# LOCO-Control.net
KiCad netlist of a schematic drawn in EAGLE
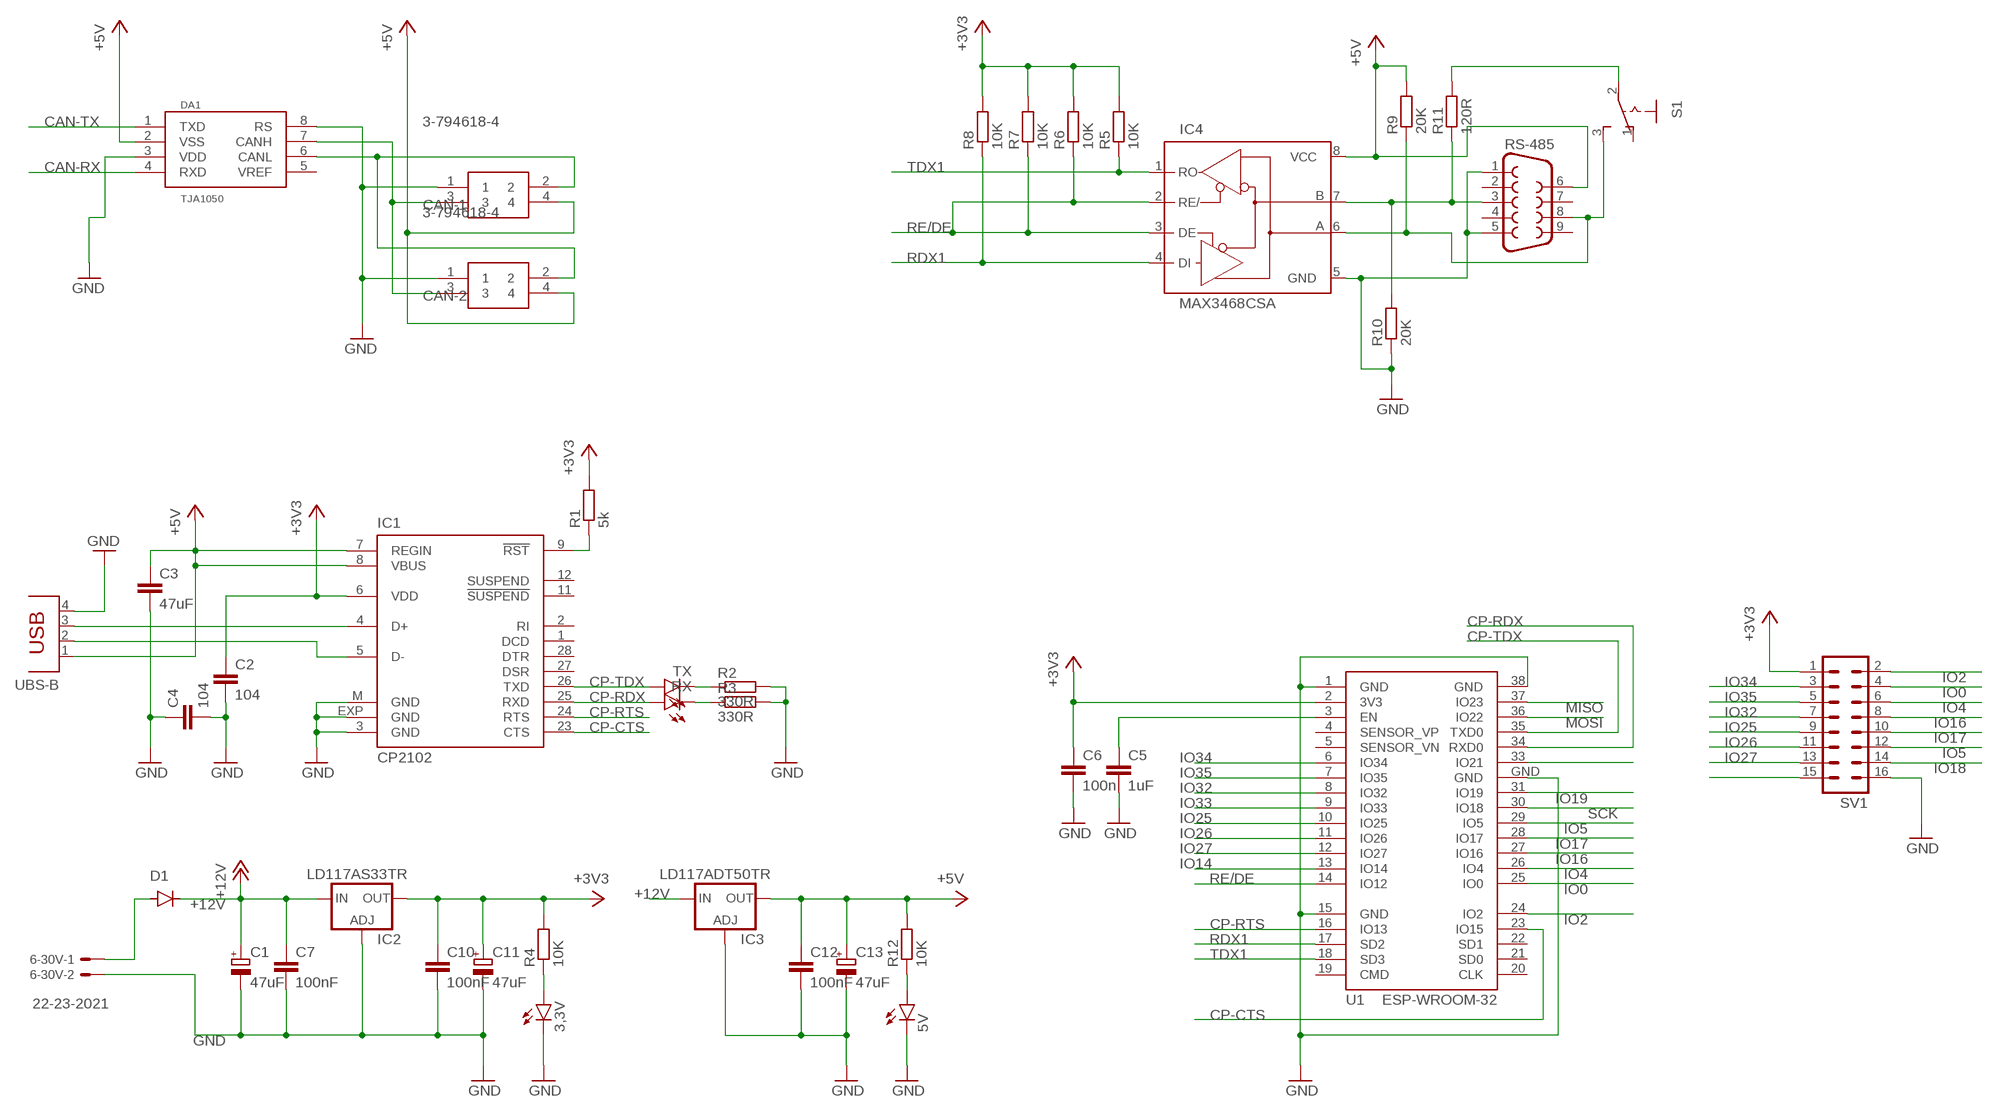
[diagram p0: schematic, sheet 1]

(export (version "E")
  (design (tool "Eeschema 10.0.6"))
  (components
    (comp (ref "3,3V")
      (value "LED")
      (footprint "eagle-import:SMARTLED-TTW")
      (libsource (lib "eagle-import") (part "LED"))
    )
    (comp (ref "5V")
      (value "LED")
      (footprint "eagle-import:SMARTLED-TTW")
      (libsource (lib "eagle-import") (part "LED"))
    )
    (comp (ref "6-30V")
      (value "22-23-2021")
      (footprint "eagle-import:22-23-2021")
      (fields (field (name "MF") "MOLEX"))
      (libsource (lib "eagle-import") (part "22-23-2021"))
    )
    (comp (ref "C1")
      (value "47uF")
      (footprint "eagle-import:B_3528-21R")
      (libsource (lib "eagle-import") (part "CPOL-EUB/3528-21R"))
    )
    (comp (ref "C2")
      (value "104")
      (footprint "eagle-import:C0402")
      (libsource (lib "eagle-import") (part "C-EUC0402"))
    )
    (comp (ref "C3")
      (value "47uF")
      (footprint "eagle-import:C0402")
      (libsource (lib "eagle-import") (part "C-EUC0402"))
    )
    (comp (ref "C4")
      (value "104")
      (footprint "eagle-import:C0402")
      (libsource (lib "eagle-import") (part "C-EUC0402"))
    )
    (comp (ref "C5")
      (value "1uF")
      (footprint "eagle-import:C0402")
      (libsource (lib "eagle-import") (part "C-EUC0402"))
    )
    (comp (ref "C6")
      (value "100n")
      (footprint "eagle-import:C0402")
      (libsource (lib "eagle-import") (part "C-EUC0402"))
    )
    (comp (ref "C7")
      (value "100nF")
      (footprint "eagle-import:C0402")
      (libsource (lib "eagle-import") (part "C-EUC0402"))
    )
    (comp (ref "C10")
      (value "100nF")
      (footprint "eagle-import:C0402")
      (libsource (lib "eagle-import") (part "C-EUC0402"))
    )
    (comp (ref "C11")
      (value "47uF")
      (footprint "eagle-import:B_3528-21R")
      (libsource (lib "eagle-import") (part "CPOL-EUB/3528-21R"))
    )
    (comp (ref "C12")
      (value "100nF")
      (footprint "eagle-import:C0402")
      (libsource (lib "eagle-import") (part "C-EUC0402"))
    )
    (comp (ref "C13")
      (value "47uF")
      (footprint "eagle-import:B_3528-21R")
      (libsource (lib "eagle-import") (part "CPOL-EUB/3528-21R"))
    )
    (comp (ref "CAN-1")
      (value "3-794618-4")
      (footprint "eagle-import:SHDRRA4W102P300_2X2_686X892X73")
      (libsource (lib "eagle-import") (part "3-794618-4"))
    )
    (comp (ref "CAN-2")
      (value "3-794618-4")
      (footprint "eagle-import:SHDRRA4W102P300_2X2_686X892X73")
      (libsource (lib "eagle-import") (part "3-794618-4"))
    )
    (comp (ref "D1")
      (value "DIODE-DO-214AC")
      (footprint "eagle-import:DO-214AC")
      (libsource (lib "eagle-import") (part "DIODE-DO-214AC"))
    )
    (comp (ref "DA1")
      (value "TJA1050")
      (footprint "eagle-import:SO08")
      (libsource (lib "eagle-import") (part "TJA1050"))
    )
    (comp (ref "IC1")
      (value "CP2102")
      (footprint "eagle-import:MLP28")
      (fields (field (name "MF") "FARNELL") (field (name "MPN") "CP2102-GM"))
      (libsource (lib "eagle-import") (part "CP2102"))
    )
    (comp (ref "IC2")
      (value "LD117AS33TR")
      (footprint "eagle-import:SOT223")
      (libsource (lib "eagle-import") (part "LD117A?S33TR"))
    )
    (comp (ref "IC3")
      (value "LD117ADT50TR")
      (footprint "eagle-import:DPACK")
      (libsource (lib "eagle-import") (part "LD117A?DT50TR"))
    )
    (comp (ref "IC4")
      (value "MAX3468CSA")
      (footprint "eagle-import:SO08")
      (fields (field (name "MPN") "MAX3468CSA+"))
      (libsource (lib "eagle-import") (part "MAX34SA68C"))
    )
    (comp (ref "R1")
      (value "5k")
      (footprint "eagle-import:MINI_MELF-0102R")
      (libsource (lib "eagle-import") (part "R-EU_MELF0102R"))
    )
    (comp (ref "R2")
      (value "330R")
      (footprint "eagle-import:MINI_MELF-0102R")
      (libsource (lib "eagle-import") (part "R-EU_MELF0102R"))
    )
    (comp (ref "R3")
      (value "330R")
      (footprint "eagle-import:MINI_MELF-0102R")
      (libsource (lib "eagle-import") (part "R-EU_MELF0102R"))
    )
    (comp (ref "R4")
      (value "10K")
      (footprint "eagle-import:MINI_MELF-0102R")
      (libsource (lib "eagle-import") (part "R-EU_MELF0102R"))
    )
    (comp (ref "R5")
      (value "10K")
      (footprint "eagle-import:MINI_MELF-0102R")
      (libsource (lib "eagle-import") (part "R-EU_MELF0102R"))
    )
    (comp (ref "R6")
      (value "10K")
      (footprint "eagle-import:MINI_MELF-0102R")
      (libsource (lib "eagle-import") (part "R-EU_MELF0102R"))
    )
    (comp (ref "R7")
      (value "10K")
      (footprint "eagle-import:MINI_MELF-0102R")
      (libsource (lib "eagle-import") (part "R-EU_MELF0102R"))
    )
    (comp (ref "R8")
      (value "10K")
      (footprint "eagle-import:MINI_MELF-0102R")
      (libsource (lib "eagle-import") (part "R-EU_MELF0102R"))
    )
    (comp (ref "R9")
      (value "20K")
      (footprint "eagle-import:MINI_MELF-0102R")
      (libsource (lib "eagle-import") (part "R-EU_MELF0102R"))
    )
    (comp (ref "R10")
      (value "20K")
      (footprint "eagle-import:MINI_MELF-0102R")
      (libsource (lib "eagle-import") (part "R-EU_MELF0102R"))
    )
    (comp (ref "R11")
      (value "120R")
      (footprint "eagle-import:MINI_MELF-0102R")
      (libsource (lib "eagle-import") (part "R-EU_MELF0102R"))
    )
    (comp (ref "R12")
      (value "10K")
      (footprint "eagle-import:MINI_MELF-0102R")
      (libsource (lib "eagle-import") (part "R-EU_MELF0102R"))
    )
    (comp (ref "RS-485")
      (value "F09H")
      (footprint "eagle-import:F09H")
      (libsource (lib "eagle-import") (part "F09H"))
    )
    (comp (ref "RX")
      (value "LED")
      (footprint "eagle-import:SMARTLED-TTW")
      (libsource (lib "eagle-import") (part "LED"))
    )
    (comp (ref "S1")
      (value "255SB")
      (footprint "eagle-import:255SB")
      (libsource (lib "eagle-import") (part "255SB"))
    )
    (comp (ref "SV1")
      (value "MA08-2")
      (footprint "eagle-import:MA08-2")
      (libsource (lib "eagle-import") (part "MA08-2"))
    )
    (comp (ref "TX")
      (value "LED")
      (footprint "eagle-import:SMARTLED-TTW")
      (libsource (lib "eagle-import") (part "LED"))
    )
    (comp (ref "U1")
      (value "ESP-WROOM-32")
      (footprint "eagle-import:ESP-WROOM-32")
      (libsource (lib "eagle-import") (part "ESP-WROOM-32"))
    )
    (comp (ref "UBS-B")
      (value "PN61729")
      (footprint "eagle-import:PN61729")
      (libsource (lib "eagle-import") (part "PN61729"))
    )
  )
  (nets
    (net (code "1") (name "+3V3") (class "Default")
      (node (ref "C10") (pin "1") (pinfunction "1_1") (pintype "passive"))
      (node (ref "C11") (pin "+") (pinfunction "+_+") (pintype "passive"))
      (node (ref "C2") (pin "1") (pinfunction "1_1") (pintype "passive"))
      (node (ref "C6") (pin "1") (pinfunction "1_1") (pintype "passive"))
      (node (ref "IC1") (pin "6") (pinfunction "VDD_6") (pintype "power_in"))
      (node (ref "IC2") (pin "4") (pinfunction "OUT_4") (pintype "passive"))
      (node (ref "R1") (pin "2") (pinfunction "2_2") (pintype "passive"))
      (node (ref "R4") (pin "2") (pinfunction "2_2") (pintype "passive"))
      (node (ref "R5") (pin "2") (pinfunction "2_2") (pintype "passive"))
      (node (ref "R6") (pin "2") (pinfunction "2_2") (pintype "passive"))
      (node (ref "R7") (pin "2") (pinfunction "2_2") (pintype "passive"))
      (node (ref "R8") (pin "2") (pinfunction "2_2") (pintype "passive"))
      (node (ref "SV1") (pin "1") (pinfunction "1_1") (pintype "passive"))
      (node (ref "U1") (pin "2") (pinfunction "3V3_2") (pintype "power_in"))
    )
    (net (code "2") (name "+5V") (class "Default")
      (node (ref "C12") (pin "1") (pinfunction "1_1") (pintype "passive"))
      (node (ref "C13") (pin "+") (pinfunction "+_+") (pintype "passive"))
      (node (ref "C3") (pin "1") (pinfunction "1_1") (pintype "passive"))
      (node (ref "CAN-1") (pin "4") (pinfunction "4_4") (pintype "bidirectional"))
      (node (ref "CAN-2") (pin "4") (pinfunction "4_4") (pintype "bidirectional"))
      (node (ref "DA1") (pin "2") (pinfunction "VSS_2") (pintype "power_in"))
      (node (ref "IC1") (pin "7") (pinfunction "REGIN_7") (pintype "passive"))
      (node (ref "IC1") (pin "8") (pinfunction "VBUS_8") (pintype "input"))
      (node (ref "IC3") (pin "4") (pinfunction "OUT_4") (pintype "passive"))
      (node (ref "IC4") (pin "8") (pinfunction "VCC_8") (pintype "power_in"))
      (node (ref "R12") (pin "2") (pinfunction "2_2") (pintype "passive"))
      (node (ref "R9") (pin "2") (pinfunction "2_2") (pintype "passive"))
      (node (ref "RS-485") (pin "6") (pinfunction "6_6") (pintype "passive"))
      (node (ref "UBS-B") (pin "1") (pinfunction "1_1") (pintype "passive"))
    )
    (net (code "3") (name "+12V") (class "Default")
      (node (ref "C1") (pin "+") (pinfunction "+_+") (pintype "passive"))
      (node (ref "C7") (pin "1") (pinfunction "1_1") (pintype "passive"))
      (node (ref "D1") (pin "C") (pinfunction "C_C") (pintype "passive"))
      (node (ref "IC2") (pin "3") (pinfunction "IN_3") (pintype "input"))
      (node (ref "IC3") (pin "3") (pinfunction "IN_3") (pintype "input"))
    )
    (net (code "4") (name "/CAN-RX") (class "Default")
      (node (ref "DA1") (pin "4") (pinfunction "RXD_4") (pintype "output"))
    )
    (net (code "5") (name "/CAN-TX") (class "Default")
      (node (ref "DA1") (pin "1") (pinfunction "TXD_1") (pintype "input"))
    )
    (net (code "6") (name "/CP-CTS") (class "Default")
      (node (ref "IC1") (pin "23") (pinfunction "CTS_23") (pintype "input"))
      (node (ref "U1") (pin "23") (pinfunction "IO15_23") (pintype "bidirectional"))
    )
    (net (code "7") (name "/CP-RDX") (class "Default")
      (node (ref "IC1") (pin "25") (pinfunction "RXD_25") (pintype "input"))
      (node (ref "RX") (pin "A@1") (pinfunction "A_A@1") (pintype "passive"))
      (node (ref "U1") (pin "34") (pinfunction "RXD0_34") (pintype "bidirectional"))
    )
    (net (code "8") (name "/CP-RTS") (class "Default")
      (node (ref "IC1") (pin "24") (pinfunction "RTS_24") (pintype "output"))
      (node (ref "U1") (pin "16") (pinfunction "IO13_16") (pintype "bidirectional"))
    )
    (net (code "9") (name "/CP-TDX") (class "Default")
      (node (ref "IC1") (pin "26") (pinfunction "TXD_26") (pintype "output"))
      (node (ref "TX") (pin "A@1") (pinfunction "A_A@1") (pintype "passive"))
      (node (ref "U1") (pin "35") (pinfunction "TXD0_35") (pintype "bidirectional"))
    )
    (net (code "10") (name "/IO0") (class "Default")
      (node (ref "SV1") (pin "4") (pinfunction "4_4") (pintype "passive"))
      (node (ref "U1") (pin "25") (pinfunction "IO0_25") (pintype "bidirectional"))
    )
    (net (code "11") (name "/IO2") (class "Default")
      (node (ref "SV1") (pin "2") (pinfunction "2_2") (pintype "passive"))
      (node (ref "U1") (pin "24") (pinfunction "IO2_24") (pintype "bidirectional"))
    )
    (net (code "12") (name "/IO4") (class "Default")
      (node (ref "SV1") (pin "6") (pinfunction "6_6") (pintype "passive"))
      (node (ref "U1") (pin "26") (pinfunction "IO4_26") (pintype "bidirectional"))
    )
    (net (code "13") (name "/IO5") (class "Default")
      (node (ref "SV1") (pin "12") (pinfunction "12_12") (pintype "passive"))
      (node (ref "U1") (pin "29") (pinfunction "IO5_29") (pintype "bidirectional"))
    )
    (net (code "14") (name "/IO14") (class "Default")
      (node (ref "SV1") (pin "15") (pinfunction "15_15") (pintype "passive"))
      (node (ref "U1") (pin "13") (pinfunction "IO14_13") (pintype "bidirectional"))
    )
    (net (code "15") (name "/IO16") (class "Default")
      (node (ref "SV1") (pin "8") (pinfunction "8_8") (pintype "passive"))
      (node (ref "U1") (pin "27") (pinfunction "IO16_27") (pintype "bidirectional"))
    )
    (net (code "16") (name "/IO17") (class "Default")
      (node (ref "SV1") (pin "10") (pinfunction "10_10") (pintype "passive"))
      (node (ref "U1") (pin "28") (pinfunction "IO17_28") (pintype "bidirectional"))
    )
    (net (code "17") (name "/IO18") (class "Default")
      (node (ref "SV1") (pin "14") (pinfunction "14_14") (pintype "passive"))
    )
    (net (code "18") (name "/IO19") (class "Default")
      (node (ref "U1") (pin "31") (pinfunction "IO19_31") (pintype "bidirectional"))
    )
    (net (code "19") (name "/IO25") (class "Default")
      (node (ref "SV1") (pin "9") (pinfunction "9_9") (pintype "passive"))
      (node (ref "U1") (pin "10") (pinfunction "IO25_10") (pintype "bidirectional"))
    )
    (net (code "20") (name "/IO26") (class "Default")
      (node (ref "SV1") (pin "11") (pinfunction "11_11") (pintype "passive"))
      (node (ref "U1") (pin "11") (pinfunction "IO26_11") (pintype "bidirectional"))
    )
    (net (code "21") (name "/IO27") (class "Default")
      (node (ref "SV1") (pin "13") (pinfunction "13_13") (pintype "passive"))
      (node (ref "U1") (pin "12") (pinfunction "IO27_12") (pintype "bidirectional"))
    )
    (net (code "22") (name "/IO32") (class "Default")
      (node (ref "SV1") (pin "7") (pinfunction "7_7") (pintype "passive"))
      (node (ref "U1") (pin "8") (pinfunction "IO32_8") (pintype "bidirectional"))
    )
    (net (code "23") (name "/IO33") (class "Default")
      (node (ref "U1") (pin "9") (pinfunction "IO33_9") (pintype "bidirectional"))
    )
    (net (code "24") (name "/IO34") (class "Default")
      (node (ref "SV1") (pin "3") (pinfunction "3_3") (pintype "passive"))
      (node (ref "U1") (pin "6") (pinfunction "IO34_6") (pintype "bidirectional"))
    )
    (net (code "25") (name "/IO35") (class "Default")
      (node (ref "SV1") (pin "5") (pinfunction "5_5") (pintype "passive"))
      (node (ref "U1") (pin "7") (pinfunction "IO35_7") (pintype "bidirectional"))
    )
    (net (code "26") (name "/MISO") (class "Default")
      (node (ref "U1") (pin "37") (pinfunction "IO23_37") (pintype "bidirectional"))
    )
    (net (code "27") (name "/MOSI") (class "Default")
      (node (ref "U1") (pin "36") (pinfunction "IO22_36") (pintype "bidirectional"))
    )
    (net (code "28") (name "/RDX1") (class "Default")
      (node (ref "IC4") (pin "4") (pinfunction "DI_4") (pintype "input"))
      (node (ref "R8") (pin "1") (pinfunction "1_1") (pintype "passive"))
      (node (ref "U1") (pin "17") (pinfunction "SD2_17") (pintype "bidirectional"))
    )
    (net (code "29") (name "/RE{slash}DE") (class "Default")
      (node (ref "IC4") (pin "2") (pinfunction "RE/_2") (pintype "input"))
      (node (ref "IC4") (pin "3") (pinfunction "DE_3") (pintype "input"))
      (node (ref "R6") (pin "1") (pinfunction "1_1") (pintype "passive"))
      (node (ref "R7") (pin "1") (pinfunction "1_1") (pintype "passive"))
      (node (ref "U1") (pin "14") (pinfunction "IO12_14") (pintype "bidirectional"))
    )
    (net (code "30") (name "/SCK") (class "Default")
      (node (ref "U1") (pin "30") (pinfunction "IO18_30") (pintype "bidirectional"))
    )
    (net (code "31") (name "/TDX1") (class "Default")
      (node (ref "IC4") (pin "1") (pinfunction "RO_1") (pintype "output"))
      (node (ref "R5") (pin "1") (pinfunction "1_1") (pintype "passive"))
      (node (ref "U1") (pin "18") (pinfunction "SD3_18") (pintype "bidirectional"))
    )
    (net (code "32") (name "GND") (class "Default")
      (node (ref "3,3V") (pin "C@1") (pinfunction "C_C@1") (pintype "passive"))
      (node (ref "5V") (pin "C@1") (pinfunction "C_C@1") (pintype "passive"))
      (node (ref "6-30V") (pin "2") (pinfunction "S_2") (pintype "passive"))
      (node (ref "C1") (pin "-") (pinfunction "-_-") (pintype "passive"))
      (node (ref "C10") (pin "2") (pinfunction "2_2") (pintype "passive"))
      (node (ref "C11") (pin "-") (pinfunction "-_-") (pintype "passive"))
      (node (ref "C12") (pin "2") (pinfunction "2_2") (pintype "passive"))
      (node (ref "C13") (pin "-") (pinfunction "-_-") (pintype "passive"))
      (node (ref "C2") (pin "2") (pinfunction "2_2") (pintype "passive"))
      (node (ref "C3") (pin "2") (pinfunction "2_2") (pintype "passive"))
      (node (ref "C4") (pin "1") (pinfunction "1_1") (pintype "passive"))
      (node (ref "C4") (pin "2") (pinfunction "2_2") (pintype "passive"))
      (node (ref "C5") (pin "2") (pinfunction "2_2") (pintype "passive"))
      (node (ref "C6") (pin "2") (pinfunction "2_2") (pintype "passive"))
      (node (ref "C7") (pin "2") (pinfunction "2_2") (pintype "passive"))
      (node (ref "CAN-1") (pin "1") (pinfunction "1_1") (pintype "bidirectional"))
      (node (ref "CAN-2") (pin "1") (pinfunction "1_1") (pintype "bidirectional"))
      (node (ref "DA1") (pin "3") (pinfunction "VDD_3") (pintype "power_in"))
      (node (ref "DA1") (pin "8") (pinfunction "RS_8") (pintype "input"))
      (node (ref "IC1") (pin "3") (pinfunction "GND_3") (pintype "power_in"))
      (node (ref "IC1") (pin "EXP") (pinfunction "GND_EXP") (pintype "power_in"))
      (node (ref "IC1") (pin "M") (pinfunction "GND_M") (pintype "power_in"))
      (node (ref "IC2") (pin "1") (pinfunction "ADJ_1") (pintype "input"))
      (node (ref "IC3") (pin "1") (pinfunction "ADJ_1") (pintype "input"))
      (node (ref "IC4") (pin "5") (pinfunction "GND_5") (pintype "power_in"))
      (node (ref "R10") (pin "1") (pinfunction "1_1") (pintype "passive"))
      (node (ref "R2") (pin "2") (pinfunction "2_2") (pintype "passive"))
      (node (ref "R3") (pin "2") (pinfunction "2_2") (pintype "passive"))
      (node (ref "RS-485") (pin "1") (pinfunction "1_1") (pintype "passive"))
      (node (ref "RS-485") (pin "5") (pinfunction "5_5") (pintype "passive"))
      (node (ref "SV1") (pin "16") (pinfunction "16_16") (pintype "passive"))
      (node (ref "U1") (pin "1") (pinfunction "GND_1") (pintype "power_in"))
      (node (ref "U1") (pin "15") (pinfunction "GND_15") (pintype "power_in"))
      (node (ref "U1") (pin "38") (pinfunction "GND_38") (pintype "power_in"))
      (node (ref "U1") (pin "GND") (pinfunction "GND_GND") (pintype "power_in"))
      (node (ref "UBS-B") (pin "4") (pinfunction "4_4") (pintype "passive"))
    )
    (net (code "33") (name "Net-(3,3V-A)") (class "Default")
      (node (ref "3,3V") (pin "A@1") (pinfunction "A_A@1") (pintype "passive"))
      (node (ref "R4") (pin "1") (pinfunction "1_1") (pintype "passive"))
    )
    (net (code "34") (name "Net-(5V-A)") (class "Default")
      (node (ref "5V") (pin "A@1") (pinfunction "A_A@1") (pintype "passive"))
      (node (ref "R12") (pin "1") (pinfunction "1_1") (pintype "passive"))
    )
    (net (code "35") (name "Net-(6-30VA-S)") (class "Default")
      (node (ref "6-30V") (pin "1") (pinfunction "S_1") (pintype "passive"))
      (node (ref "D1") (pin "A") (pinfunction "A_A") (pintype "passive"))
    )
    (net (code "36") (name "Net-(DA1-CANH)") (class "Default")
      (node (ref "CAN-1") (pin "3") (pinfunction "3_3") (pintype "bidirectional"))
      (node (ref "CAN-2") (pin "3") (pinfunction "3_3") (pintype "bidirectional"))
      (node (ref "DA1") (pin "7") (pinfunction "CANH_7") (pintype "bidirectional"))
    )
    (net (code "37") (name "Net-(DA1-CANL)") (class "Default")
      (node (ref "CAN-1") (pin "2") (pinfunction "2_2") (pintype "bidirectional"))
      (node (ref "CAN-2") (pin "2") (pinfunction "2_2") (pintype "bidirectional"))
      (node (ref "DA1") (pin "6") (pinfunction "CANL_6") (pintype "bidirectional"))
    )
    (net (code "38") (name "Net-(IC1-D+)") (class "Default")
      (node (ref "IC1") (pin "4") (pinfunction "D+_4") (pintype "bidirectional"))
      (node (ref "UBS-B") (pin "3") (pinfunction "3_3") (pintype "passive"))
    )
    (net (code "39") (name "Net-(IC1-D-)") (class "Default")
      (node (ref "IC1") (pin "5") (pinfunction "D-_5") (pintype "bidirectional"))
      (node (ref "UBS-B") (pin "2") (pinfunction "2_2") (pintype "passive"))
    )
    (net (code "40") (name "Net-(IC1-~{RST})") (class "Default")
      (node (ref "IC1") (pin "9") (pinfunction "~{RST}_9") (pintype "bidirectional"))
      (node (ref "R1") (pin "1") (pinfunction "1_1") (pintype "passive"))
    )
    (net (code "41") (name "Net-(IC4-A)") (class "Default")
      (node (ref "IC4") (pin "6") (pinfunction "A_6") (pintype "passive"))
      (node (ref "R9") (pin "1") (pinfunction "1_1") (pintype "passive"))
      (node (ref "RS-485") (pin "8") (pinfunction "8_8") (pintype "passive"))
      (node (ref "S1") (pin "3") (pinfunction "S_3") (pintype "passive"))
    )
    (net (code "42") (name "Net-(IC4-B)") (class "Default")
      (node (ref "IC4") (pin "7") (pinfunction "B_7") (pintype "passive"))
      (node (ref "R10") (pin "2") (pinfunction "2_2") (pintype "passive"))
      (node (ref "R11") (pin "1") (pinfunction "1_1") (pintype "passive"))
      (node (ref "RS-485") (pin "3") (pinfunction "3_3") (pintype "passive"))
    )
    (net (code "43") (name "Net-(RX-C)") (class "Default")
      (node (ref "R3") (pin "1") (pinfunction "1_1") (pintype "passive"))
      (node (ref "RX") (pin "C@1") (pinfunction "C_C@1") (pintype "passive"))
    )
    (net (code "44") (name "Net-(S1-P)") (class "Default")
      (node (ref "R11") (pin "2") (pinfunction "2_2") (pintype "passive"))
      (node (ref "S1") (pin "2") (pinfunction "P_2") (pintype "passive"))
    )
    (net (code "45") (name "Net-(TX-C)") (class "Default")
      (node (ref "R2") (pin "1") (pinfunction "1_1") (pintype "passive"))
      (node (ref "TX") (pin "C@1") (pinfunction "C_C@1") (pintype "passive"))
    )
    (net (code "46") (name "Net-(U1-EN)") (class "Default")
      (node (ref "C5") (pin "1") (pinfunction "1_1") (pintype "passive"))
      (node (ref "U1") (pin "3") (pinfunction "EN_3") (pintype "input"))
    )
    (net (code "47") (name "unconnected-(DA1-VREF-Pad5)") (class "Default")
      (node (ref "DA1") (pin "5") (pinfunction "VREF_5") (pintype "passive"))
    )
    (net (code "48") (name "unconnected-(IC1-DCD-Pad1)") (class "Default")
      (node (ref "IC1") (pin "1") (pinfunction "DCD_1") (pintype "input"))
    )
    (net (code "49") (name "unconnected-(IC1-DSR-Pad27)") (class "Default")
      (node (ref "IC1") (pin "27") (pinfunction "DSR_27") (pintype "input"))
    )
    (net (code "50") (name "unconnected-(IC1-DTR-Pad28)") (class "Default")
      (node (ref "IC1") (pin "28") (pinfunction "DTR_28") (pintype "output"))
    )
    (net (code "51") (name "unconnected-(IC1-RI-Pad2)") (class "Default")
      (node (ref "IC1") (pin "2") (pinfunction "RI_2") (pintype "input"))
    )
    (net (code "52") (name "unconnected-(IC1-SUSPEND-Pad12)") (class "Default")
      (node (ref "IC1") (pin "12") (pinfunction "SUSPEND_12") (pintype "output"))
    )
    (net (code "53") (name "unconnected-(IC1-~{SUSPEND}-Pad11)") (class "Default")
      (node (ref "IC1") (pin "11") (pinfunction "~{SUSPEND}_11") (pintype "output"))
    )
    (net (code "54") (name "unconnected-(RS-485-Pad2)") (class "Default")
      (node (ref "RS-485") (pin "2") (pinfunction "2_2") (pintype "passive"))
    )
    (net (code "55") (name "unconnected-(RS-485-Pad4)") (class "Default")
      (node (ref "RS-485") (pin "4") (pinfunction "4_4") (pintype "passive"))
    )
    (net (code "56") (name "unconnected-(RS-485-Pad7)") (class "Default")
      (node (ref "RS-485") (pin "7") (pinfunction "7_7") (pintype "passive"))
    )
    (net (code "57") (name "unconnected-(RS-485-Pad9)") (class "Default")
      (node (ref "RS-485") (pin "9") (pinfunction "9_9") (pintype "passive"))
    )
    (net (code "58") (name "unconnected-(S1-O-Pad1)") (class "Default")
      (node (ref "S1") (pin "1") (pinfunction "O_1") (pintype "passive"))
    )
    (net (code "59") (name "unconnected-(U1-CLK-Pad20)") (class "Default")
      (node (ref "U1") (pin "20") (pinfunction "CLK_20") (pintype "bidirectional"))
    )
    (net (code "60") (name "unconnected-(U1-CMD-Pad19)") (class "Default")
      (node (ref "U1") (pin "19") (pinfunction "CMD_19") (pintype "bidirectional"))
    )
    (net (code "61") (name "unconnected-(U1-IO21-Pad33)") (class "Default")
      (node (ref "U1") (pin "33") (pinfunction "IO21_33") (pintype "bidirectional"))
    )
    (net (code "62") (name "unconnected-(U1-SD0-Pad21)") (class "Default")
      (node (ref "U1") (pin "21") (pinfunction "SD0_21") (pintype "bidirectional"))
    )
    (net (code "63") (name "unconnected-(U1-SD1-Pad22)") (class "Default")
      (node (ref "U1") (pin "22") (pinfunction "SD1_22") (pintype "bidirectional"))
    )
    (net (code "64") (name "unconnected-(U1-SENSOR_VN-Pad5)") (class "Default")
      (node (ref "U1") (pin "5") (pinfunction "SENSOR_VN_5") (pintype "bidirectional"))
    )
    (net (code "65") (name "unconnected-(U1-SENSOR_VP-Pad4)") (class "Default")
      (node (ref "U1") (pin "4") (pinfunction "SENSOR_VP_4") (pintype "bidirectional"))
    )
  )
)
